# Amp-Rev1.net
KiCad netlist of a schematic drawn in EAGLE
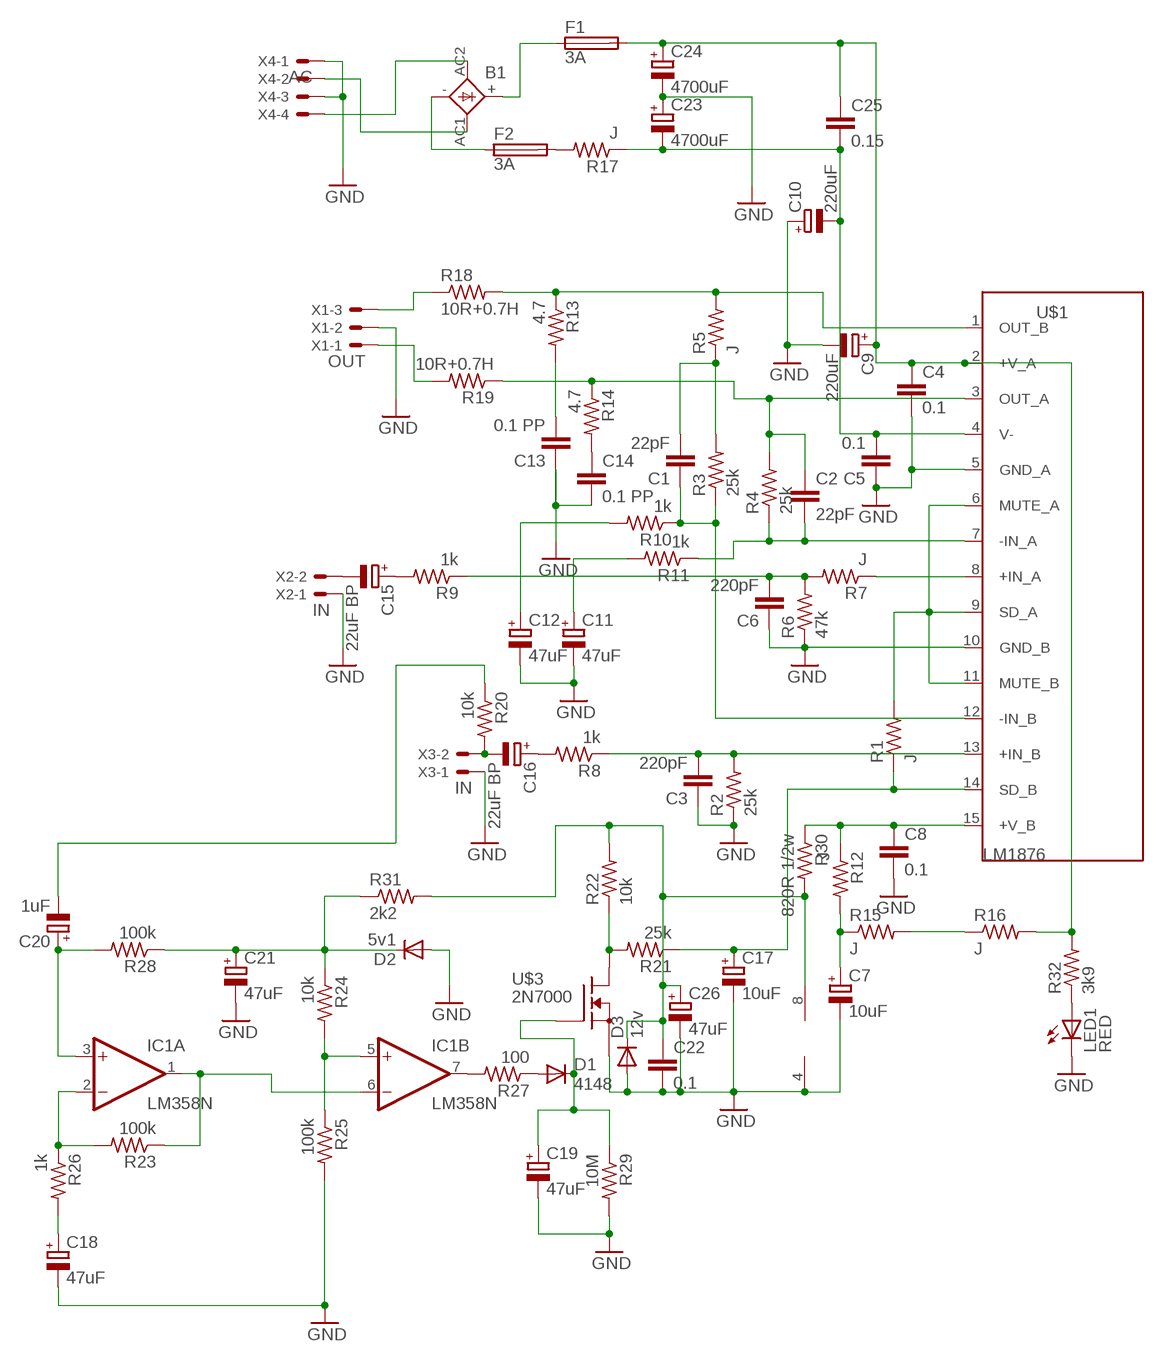
[diagram p0: schematic, sheet 1]

(export (version "E")
  (design (tool "Eeschema 10.0.6"))
  (components
    (comp (ref "B1")
      (value "GBU4")
      (footprint "eagle-import:GBU4S")
      (libsource (lib "eagle-import") (part "GBU4"))
    )
    (comp (ref "C1")
      (value "22pF")
      (footprint "eagle-import:C075-032X103")
      (libsource (lib "eagle-import") (part "C-EU075-032X103"))
    )
    (comp (ref "C2")
      (value "22pF")
      (footprint "eagle-import:C075-032X103")
      (libsource (lib "eagle-import") (part "C-EU075-032X103"))
    )
    (comp (ref "C3")
      (value "220pF")
      (footprint "eagle-import:C1210")
      (libsource (lib "eagle-import") (part "C-EUC1210"))
    )
    (comp (ref "C4")
      (value "0.1")
      (footprint "eagle-import:C050-025X075")
      (libsource (lib "eagle-import") (part "C-EU050-025X075"))
    )
    (comp (ref "C5")
      (value "0.1")
      (footprint "eagle-import:C050-025X075")
      (libsource (lib "eagle-import") (part "C-EU050-025X075"))
    )
    (comp (ref "C6")
      (value "220pF")
      (footprint "eagle-import:C1210")
      (libsource (lib "eagle-import") (part "C-EUC1210"))
    )
    (comp (ref "C7")
      (value "10uF")
      (footprint "eagle-import:E2,5-7")
      (libsource (lib "eagle-import") (part "CPOL-EUE2.5-7"))
    )
    (comp (ref "C8")
      (value "0.1")
      (footprint "eagle-import:C050-025X075")
      (libsource (lib "eagle-import") (part "C-EU050-025X075"))
    )
    (comp (ref "C9")
      (value "220uF")
      (footprint "eagle-import:E5-8,5")
      (libsource (lib "eagle-import") (part "CPOL-EUE5-8.5"))
    )
    (comp (ref "C10")
      (value "220uF")
      (footprint "eagle-import:E5-8,5")
      (libsource (lib "eagle-import") (part "CPOL-EUE5-8.5"))
    )
    (comp (ref "C11")
      (value "47uF")
      (footprint "eagle-import:E2,5-7")
      (libsource (lib "eagle-import") (part "CPOL-EUE2.5-7"))
    )
    (comp (ref "C12")
      (value "47uF")
      (footprint "eagle-import:E2,5-7")
      (libsource (lib "eagle-import") (part "CPOL-EUE2.5-7"))
    )
    (comp (ref "C13")
      (value "0.1 PP")
      (footprint "eagle-import:C050-055X075")
      (libsource (lib "eagle-import") (part "C-EU050-055X075"))
    )
    (comp (ref "C14")
      (value "0.1 PP")
      (footprint "eagle-import:C050-055X075")
      (libsource (lib "eagle-import") (part "C-EU050-055X075"))
    )
    (comp (ref "C15")
      (value "22uF BP")
      (footprint "eagle-import:E2,5-7")
      (libsource (lib "eagle-import") (part "CPOL-EUE2.5-7"))
    )
    (comp (ref "C16")
      (value "22uF BP")
      (footprint "eagle-import:E2,5-7")
      (libsource (lib "eagle-import") (part "CPOL-EUE2.5-7"))
    )
    (comp (ref "C17")
      (value "10uF")
      (footprint "eagle-import:E2,5-6")
      (libsource (lib "eagle-import") (part "CPOL-EUE2.5-6"))
    )
    (comp (ref "C18")
      (value "47uF")
      (footprint "eagle-import:E2,5-7")
      (libsource (lib "eagle-import") (part "CPOL-EUE2.5-7"))
    )
    (comp (ref "C19")
      (value "47uF")
      (footprint "eagle-import:E2,5-7")
      (libsource (lib "eagle-import") (part "CPOL-EUE2.5-7"))
    )
    (comp (ref "C20")
      (value "1uF")
      (footprint "eagle-import:E2,5-6")
      (libsource (lib "eagle-import") (part "CPOL-EUE2.5-6"))
    )
    (comp (ref "C21")
      (value "47uF")
      (footprint "eagle-import:E2,5-7")
      (libsource (lib "eagle-import") (part "CPOL-EUE2.5-7"))
    )
    (comp (ref "C22")
      (value "0.1")
      (footprint "eagle-import:C1206")
      (libsource (lib "eagle-import") (part "C-EUC1206"))
    )
    (comp (ref "C23")
      (value "4700uF")
      (footprint "eagle-import:E7,5-16")
      (libsource (lib "eagle-import") (part "CPOL-EUE7.5-16"))
    )
    (comp (ref "C24")
      (value "4700uF")
      (footprint "eagle-import:E7,5-16")
      (libsource (lib "eagle-import") (part "CPOL-EUE7.5-16"))
    )
    (comp (ref "C25")
      (value "0.15")
      (footprint "eagle-import:C075-032X103")
      (libsource (lib "eagle-import") (part "C-EU075-032X103"))
    )
    (comp (ref "C26")
      (value "47uF")
      (footprint "eagle-import:E2,5-7")
      (libsource (lib "eagle-import") (part "CPOL-EUE2.5-7"))
    )
    (comp (ref "D1")
      (value "4148")
      (footprint "eagle-import:DO35-7")
      (libsource (lib "eagle-import") (part "1N4148DO35-7"))
    )
    (comp (ref "D2")
      (value "5v1")
      (footprint "eagle-import:DO35-10")
      (libsource (lib "eagle-import") (part "1N4148DO35-10"))
    )
    (comp (ref "D3")
      (value "12v")
      (footprint "eagle-import:DO35-10")
      (libsource (lib "eagle-import") (part "1N4148DO35-10"))
    )
    (comp (ref "F1")
      (value "3A")
      (footprint "eagle-import:19560")
      (fields (field (name "MPN") "56000001009"))
      (libsource (lib "eagle-import") (part "19560"))
    )
    (comp (ref "F2")
      (value "3A")
      (footprint "eagle-import:19560")
      (fields (field (name "MPN") "56000001009"))
      (libsource (lib "eagle-import") (part "19560"))
    )
    (comp (ref "IC1")
      (value "LM358N")
      (footprint "eagle-import:DIL08")
      (libsource (lib "eagle-import") (part "LM358N"))
    )
    (comp (ref "LED1")
      (value "RED")
      (footprint "eagle-import:LED3MM")
      (fields (field (name "MF") "VISHAY SEMICONDUCTOR"))
      (libsource (lib "eagle-import") (part "TLLR4400"))
    )
    (comp (ref "R1")
      (value "J")
      (footprint "eagle-import:0207_12")
      (libsource (lib "eagle-import") (part "R-US_0207/12"))
    )
    (comp (ref "R2")
      (value "25k")
      (footprint "eagle-import:R1210")
      (libsource (lib "eagle-import") (part "R-US_R1210"))
    )
    (comp (ref "R3")
      (value "25k")
      (footprint "eagle-import:0207_10")
      (libsource (lib "eagle-import") (part "R-US_0207/10"))
    )
    (comp (ref "R4")
      (value "25k")
      (footprint "eagle-import:0207_10")
      (libsource (lib "eagle-import") (part "R-US_0207/10"))
    )
    (comp (ref "R5")
      (value "J")
      (footprint "eagle-import:0207_10")
      (libsource (lib "eagle-import") (part "R-US_0207/10"))
    )
    (comp (ref "R6")
      (value "47k")
      (footprint "eagle-import:M1206")
      (libsource (lib "eagle-import") (part "R-US_M1206"))
    )
    (comp (ref "R7")
      (value "J")
      (footprint "eagle-import:0204_7")
      (libsource (lib "eagle-import") (part "R-US_0204/7"))
    )
    (comp (ref "R8")
      (value "1k")
      (footprint "eagle-import:0207_10")
      (libsource (lib "eagle-import") (part "R-US_0207/10"))
    )
    (comp (ref "R9")
      (value "1k")
      (footprint "eagle-import:0207_12")
      (libsource (lib "eagle-import") (part "R-US_0207/12"))
    )
    (comp (ref "R10")
      (value "1k")
      (footprint "eagle-import:0204_7")
      (libsource (lib "eagle-import") (part "R-US_0204/7"))
    )
    (comp (ref "R11")
      (value "1k")
      (footprint "eagle-import:0207_10")
      (libsource (lib "eagle-import") (part "R-US_0207/10"))
    )
    (comp (ref "R12")
      (value "J")
      (footprint "eagle-import:0207_12")
      (libsource (lib "eagle-import") (part "R-US_0207/12"))
    )
    (comp (ref "R13")
      (value "4.7")
      (footprint "eagle-import:0207_12")
      (libsource (lib "eagle-import") (part "R-US_0207/12"))
    )
    (comp (ref "R14")
      (value "4.7")
      (footprint "eagle-import:0207_12")
      (libsource (lib "eagle-import") (part "R-US_0207/12"))
    )
    (comp (ref "R15")
      (value "J")
      (footprint "eagle-import:0207_12")
      (libsource (lib "eagle-import") (part "R-US_0207/12"))
    )
    (comp (ref "R16")
      (value "J")
      (footprint "eagle-import:0207_12")
      (libsource (lib "eagle-import") (part "R-US_0207/12"))
    )
    (comp (ref "R17")
      (value "J")
      (footprint "eagle-import:0207_10")
      (libsource (lib "eagle-import") (part "R-US_0207/10"))
    )
    (comp (ref "R18")
      (value "10R+0.7H")
      (footprint "eagle-import:0207_12")
      (libsource (lib "eagle-import") (part "R-US_0207/12"))
    )
    (comp (ref "R19")
      (value "10R+0.7H")
      (footprint "eagle-import:0207_12")
      (libsource (lib "eagle-import") (part "R-US_0207/12"))
    )
    (comp (ref "R20")
      (value "10k")
      (footprint "eagle-import:0204_7")
      (libsource (lib "eagle-import") (part "R-US_0204/7"))
    )
    (comp (ref "R21")
      (value "25k")
      (footprint "eagle-import:0204_7")
      (libsource (lib "eagle-import") (part "R-US_0204/7"))
    )
    (comp (ref "R22")
      (value "10k")
      (footprint "eagle-import:0204_7")
      (libsource (lib "eagle-import") (part "R-US_0204/7"))
    )
    (comp (ref "R23")
      (value "100k")
      (footprint "eagle-import:0204_5")
      (libsource (lib "eagle-import") (part "R-US_0204/5"))
    )
    (comp (ref "R24")
      (value "10k")
      (footprint "eagle-import:0207_10")
      (libsource (lib "eagle-import") (part "R-US_0207/10"))
    )
    (comp (ref "R25")
      (value "100k")
      (footprint "eagle-import:0204_5")
      (libsource (lib "eagle-import") (part "R-US_0204/5"))
    )
    (comp (ref "R26")
      (value "1k")
      (footprint "eagle-import:0207_10")
      (libsource (lib "eagle-import") (part "R-US_0207/10"))
    )
    (comp (ref "R27")
      (value "100")
      (footprint "eagle-import:0204_7")
      (libsource (lib "eagle-import") (part "R-US_0204/7"))
    )
    (comp (ref "R28")
      (value "100k")
      (footprint "eagle-import:0204_5")
      (libsource (lib "eagle-import") (part "R-US_0204/5"))
    )
    (comp (ref "R29")
      (value "10M")
      (footprint "eagle-import:0207_10")
      (libsource (lib "eagle-import") (part "R-US_0207/10"))
    )
    (comp (ref "R30")
      (value "820R 1/2w")
      (footprint "eagle-import:0207_10")
      (libsource (lib "eagle-import") (part "R-US_0207/10"))
    )
    (comp (ref "R31")
      (value "2k2")
      (footprint "eagle-import:0309_10")
      (libsource (lib "eagle-import") (part "R-US_0309/10"))
    )
    (comp (ref "R32")
      (value "3k9")
      (footprint "eagle-import:0207_10")
      (libsource (lib "eagle-import") (part "R-US_0207/10"))
    )
    (comp (ref "U$1")
      (value "LM1876")
      (footprint "eagle-import:MULTIWATT-15")
      (libsource (lib "eagle-import") (part "LM1876"))
    )
    (comp (ref "U$3")
      (value "2N7000")
      (footprint "eagle-import:TO92-")
      (libsource (lib "eagle-import") (part "2N7000"))
    )
    (comp (ref "X1")
      (value "OUT")
      (footprint "eagle-import:22-23-2031")
      (fields (field (name "MF") "MOLEX") (field (name "MPN") "22-23-2031"))
      (libsource (lib "eagle-import") (part "22-23-2031"))
    )
    (comp (ref "X2")
      (value "IN")
      (footprint "eagle-import:22-23-2021")
      (fields (field (name "MF") "MOLEX") (field (name "MPN") "22-23-2021"))
      (libsource (lib "eagle-import") (part "22-23-2021"))
    )
    (comp (ref "X3")
      (value "IN")
      (footprint "eagle-import:22-23-2021")
      (fields (field (name "MF") "MOLEX") (field (name "MPN") "22-23-2021"))
      (libsource (lib "eagle-import") (part "22-23-2021"))
    )
    (comp (ref "X4")
      (value "AC")
      (footprint "eagle-import:5566-4")
      (libsource (lib "eagle-import") (part "5566-4"))
    )
  )
  (nets
    (net (code "1") (name "GND") (class "Default")
      (node (ref "C10") (pin "+") (pinfunction "+_+") (pintype "passive"))
      (node (ref "C11") (pin "-") (pinfunction "-_-") (pintype "passive"))
      (node (ref "C12") (pin "-") (pinfunction "-_-") (pintype "passive"))
      (node (ref "C13") (pin "1") (pinfunction "1_1") (pintype "passive"))
      (node (ref "C14") (pin "2") (pinfunction "2_2") (pintype "passive"))
      (node (ref "C17") (pin "-") (pinfunction "-_-") (pintype "passive"))
      (node (ref "C18") (pin "-") (pinfunction "-_-") (pintype "passive"))
      (node (ref "C19") (pin "-") (pinfunction "-_-") (pintype "passive"))
      (node (ref "C21") (pin "-") (pinfunction "-_-") (pintype "passive"))
      (node (ref "C22") (pin "2") (pinfunction "2_2") (pintype "passive"))
      (node (ref "C23") (pin "+") (pinfunction "+_+") (pintype "passive"))
      (node (ref "C24") (pin "-") (pinfunction "-_-") (pintype "passive"))
      (node (ref "C26") (pin "-") (pinfunction "-_-") (pintype "passive"))
      (node (ref "C3") (pin "1") (pinfunction "1_1") (pintype "passive"))
      (node (ref "C4") (pin "2") (pinfunction "2_2") (pintype "passive"))
      (node (ref "C5") (pin "1") (pinfunction "1_1") (pintype "passive"))
      (node (ref "C6") (pin "1") (pinfunction "1_1") (pintype "passive"))
      (node (ref "C7") (pin "-") (pinfunction "-_-") (pintype "passive"))
      (node (ref "C8") (pin "2") (pinfunction "2_2") (pintype "passive"))
      (node (ref "C9") (pin "-") (pinfunction "-_-") (pintype "passive"))
      (node (ref "D2") (pin "A") (pinfunction "A_A") (pintype "passive"))
      (node (ref "D3") (pin "A") (pinfunction "A_A") (pintype "passive"))
      (node (ref "IC1") (pin "4") (pinfunction "V-_4") (pintype "power_in"))
      (node (ref "LED1") (pin "K") (pinfunction "C_K") (pintype "passive"))
      (node (ref "R2") (pin "1") (pinfunction "1_1") (pintype "passive"))
      (node (ref "R25") (pin "2") (pinfunction "2_2") (pintype "passive"))
      (node (ref "R29") (pin "2") (pinfunction "2_2") (pintype "passive"))
      (node (ref "R6") (pin "1") (pinfunction "1_1") (pintype "passive"))
      (node (ref "U$1") (pin "10") (pinfunction "GND_B_10") (pintype "passive"))
      (node (ref "U$1") (pin "5") (pinfunction "GND_A_5") (pintype "passive"))
      (node (ref "U$3") (pin "3") (pinfunction "S_3") (pintype "passive"))
      (node (ref "X1") (pin "2") (pinfunction "S_2") (pintype "passive"))
      (node (ref "X2") (pin "1") (pinfunction "S_1") (pintype "passive"))
      (node (ref "X3") (pin "1") (pinfunction "S_1") (pintype "passive"))
      (node (ref "X4") (pin "1") (pinfunction "S_1") (pintype "passive"))
      (node (ref "X4") (pin "3") (pinfunction "S_3") (pintype "passive"))
    )
    (net (code "2") (name "Net-(B1-AC1)") (class "Default")
      (node (ref "B1") (pin "AC2") (pinfunction "AC1_AC2") (pintype "passive"))
      (node (ref "X4") (pin "4") (pinfunction "S_4") (pintype "passive"))
    )
    (net (code "3") (name "Net-(B1-AC2)") (class "Default")
      (node (ref "B1") (pin "AC1") (pinfunction "AC2_AC1") (pintype "passive"))
      (node (ref "X4") (pin "2") (pinfunction "S_2") (pintype "passive"))
    )
    (net (code "4") (name "Net-(B1-Pad+)") (class "Default")
      (node (ref "B1") (pin "+") (pinfunction "+_+") (pintype "passive"))
      (node (ref "F1") (pin "1") (pinfunction "1_1") (pintype "passive"))
    )
    (net (code "5") (name "Net-(B1-Pad-)") (class "Default")
      (node (ref "B1") (pin "-") (pinfunction "-_-") (pintype "passive"))
      (node (ref "F2") (pin "1") (pinfunction "1_1") (pintype "passive"))
    )
    (net (code "6") (name "Net-(C1-Pad2)") (class "Default")
      (node (ref "C1") (pin "2") (pinfunction "2_2") (pintype "passive"))
      (node (ref "R3") (pin "2") (pinfunction "2_2") (pintype "passive"))
      (node (ref "R5") (pin "1") (pinfunction "1_1") (pintype "passive"))
    )
    (net (code "7") (name "Net-(C6-Pad2)") (class "Default")
      (node (ref "C6") (pin "2") (pinfunction "2_2") (pintype "passive"))
      (node (ref "R6") (pin "2") (pinfunction "2_2") (pintype "passive"))
      (node (ref "R7") (pin "2") (pinfunction "2_2") (pintype "passive"))
      (node (ref "R9") (pin "1") (pinfunction "1_1") (pintype "passive"))
    )
    (net (code "8") (name "Net-(C7-Pad+)") (class "Default")
      (node (ref "C7") (pin "+") (pinfunction "+_+") (pintype "passive"))
      (node (ref "R12") (pin "2") (pinfunction "2_2") (pintype "passive"))
      (node (ref "R15") (pin "1") (pinfunction "1_1") (pintype "passive"))
    )
    (net (code "9") (name "Net-(C11-Pad+)") (class "Default")
      (node (ref "C11") (pin "+") (pinfunction "+_+") (pintype "passive"))
      (node (ref "R11") (pin "2") (pinfunction "2_2") (pintype "passive"))
    )
    (net (code "10") (name "Net-(C12-Pad+)") (class "Default")
      (node (ref "C12") (pin "+") (pinfunction "+_+") (pintype "passive"))
      (node (ref "R10") (pin "2") (pinfunction "2_2") (pintype "passive"))
    )
    (net (code "11") (name "Net-(C13-Pad2)") (class "Default")
      (node (ref "C13") (pin "2") (pinfunction "2_2") (pintype "passive"))
      (node (ref "R13") (pin "2") (pinfunction "2_2") (pintype "passive"))
    )
    (net (code "12") (name "Net-(C14-Pad1)") (class "Default")
      (node (ref "C14") (pin "1") (pinfunction "1_1") (pintype "passive"))
      (node (ref "R14") (pin "2") (pinfunction "2_2") (pintype "passive"))
    )
    (net (code "13") (name "Net-(C15-Pad+)") (class "Default")
      (node (ref "C15") (pin "+") (pinfunction "+_+") (pintype "passive"))
      (node (ref "R9") (pin "2") (pinfunction "2_2") (pintype "passive"))
    )
    (net (code "14") (name "Net-(C16-Pad+)") (class "Default")
      (node (ref "C16") (pin "+") (pinfunction "+_+") (pintype "passive"))
      (node (ref "R8") (pin "2") (pinfunction "2_2") (pintype "passive"))
    )
    (net (code "15") (name "Net-(C18-Pad+)") (class "Default")
      (node (ref "C18") (pin "+") (pinfunction "+_+") (pintype "passive"))
      (node (ref "R26") (pin "2") (pinfunction "2_2") (pintype "passive"))
    )
    (net (code "16") (name "Net-(C20-Pad-)") (class "Default")
      (node (ref "C20") (pin "-") (pinfunction "-_-") (pintype "passive"))
      (node (ref "R20") (pin "1") (pinfunction "1_1") (pintype "passive"))
    )
    (net (code "17") (name "Net-(C21-Pad+)") (class "Default")
      (node (ref "C21") (pin "+") (pinfunction "+_+") (pintype "passive"))
      (node (ref "D2") (pin "C") (pinfunction "C_C") (pintype "passive"))
      (node (ref "R24") (pin "1") (pinfunction "1_1") (pintype "passive"))
      (node (ref "R28") (pin "1") (pinfunction "1_1") (pintype "passive"))
      (node (ref "R31") (pin "1") (pinfunction "1_1") (pintype "passive"))
    )
    (net (code "18") (name "Net-(D1-PadA)") (class "Default")
      (node (ref "D1") (pin "A") (pinfunction "A_A") (pintype "passive"))
      (node (ref "R27") (pin "1") (pinfunction "1_1") (pintype "passive"))
    )
    (net (code "19") (name "Net-(F2-Pad2)") (class "Default")
      (node (ref "F2") (pin "2") (pinfunction "2_2") (pintype "passive"))
      (node (ref "R17") (pin "2") (pinfunction "2_2") (pintype "passive"))
    )
    (net (code "20") (name "Net-(IC1A-+IN)") (class "Default")
      (node (ref "C20") (pin "+") (pinfunction "+_+") (pintype "passive"))
      (node (ref "IC1") (pin "3") (pinfunction "+IN_3") (pintype "input"))
      (node (ref "R28") (pin "2") (pinfunction "2_2") (pintype "passive"))
    )
    (net (code "21") (name "Net-(IC1A--IN)") (class "Default")
      (node (ref "IC1") (pin "2") (pinfunction "-IN_2") (pintype "input"))
      (node (ref "R23") (pin "2") (pinfunction "2_2") (pintype "passive"))
      (node (ref "R26") (pin "1") (pinfunction "1_1") (pintype "passive"))
    )
    (net (code "22") (name "Net-(IC1A-OUT)") (class "Default")
      (node (ref "IC1") (pin "1") (pinfunction "OUT_1") (pintype "output"))
      (node (ref "IC1") (pin "6") (pinfunction "-IN_6") (pintype "input"))
      (node (ref "R23") (pin "1") (pinfunction "1_1") (pintype "passive"))
    )
    (net (code "23") (name "Net-(IC1B-+IN)") (class "Default")
      (node (ref "IC1") (pin "5") (pinfunction "+IN_5") (pintype "input"))
      (node (ref "R24") (pin "2") (pinfunction "2_2") (pintype "passive"))
      (node (ref "R25") (pin "1") (pinfunction "1_1") (pintype "passive"))
    )
    (net (code "24") (name "Net-(IC1B-OUT)") (class "Default")
      (node (ref "IC1") (pin "7") (pinfunction "OUT_7") (pintype "output"))
      (node (ref "R27") (pin "2") (pinfunction "2_2") (pintype "passive"))
    )
    (net (code "25") (name "Net-(IC1C-V+)") (class "Default")
      (node (ref "C22") (pin "1") (pinfunction "1_1") (pintype "passive"))
      (node (ref "C26") (pin "+") (pinfunction "+_+") (pintype "passive"))
      (node (ref "D3") (pin "C") (pinfunction "C_C") (pintype "passive"))
      (node (ref "IC1") (pin "8") (pinfunction "V+_8") (pintype "power_in"))
      (node (ref "R22") (pin "2") (pinfunction "2_2") (pintype "passive"))
      (node (ref "R30") (pin "2") (pinfunction "2_2") (pintype "passive"))
      (node (ref "R31") (pin "2") (pinfunction "2_2") (pintype "passive"))
    )
    (net (code "26") (name "Net-(LED1-PadA)") (class "Default")
      (node (ref "LED1") (pin "A") (pinfunction "A_A") (pintype "passive"))
      (node (ref "R32") (pin "1") (pinfunction "1_1") (pintype "passive"))
    )
    (net (code "27") (name "Net-(R15-Pad2)") (class "Default")
      (node (ref "R15") (pin "2") (pinfunction "2_2") (pintype "passive"))
      (node (ref "R16") (pin "1") (pinfunction "1_1") (pintype "passive"))
    )
    (net (code "28") (name "Net-(U$1-+IN_A)") (class "Default")
      (node (ref "R7") (pin "1") (pinfunction "1_1") (pintype "passive"))
      (node (ref "U$1") (pin "8") (pinfunction "+IN_A_8") (pintype "passive"))
    )
    (net (code "29") (name "Net-(U$1-+IN_B)") (class "Default")
      (node (ref "C3") (pin "2") (pinfunction "2_2") (pintype "passive"))
      (node (ref "R2") (pin "2") (pinfunction "2_2") (pintype "passive"))
      (node (ref "R8") (pin "1") (pinfunction "1_1") (pintype "passive"))
      (node (ref "U$1") (pin "13") (pinfunction "+IN_B_13") (pintype "passive"))
    )
    (net (code "30") (name "Net-(U$1-+V_A)") (class "Default")
      (node (ref "C24") (pin "+") (pinfunction "+_+") (pintype "passive"))
      (node (ref "C25") (pin "1") (pinfunction "1_1") (pintype "passive"))
      (node (ref "C4") (pin "1") (pinfunction "1_1") (pintype "passive"))
      (node (ref "C9") (pin "+") (pinfunction "+_+") (pintype "passive"))
      (node (ref "F1") (pin "2") (pinfunction "2_2") (pintype "passive"))
      (node (ref "R16") (pin "2") (pinfunction "2_2") (pintype "passive"))
      (node (ref "R32") (pin "2") (pinfunction "2_2") (pintype "passive"))
      (node (ref "U$1") (pin "2") (pinfunction "+V_A_2") (pintype "passive"))
    )
    (net (code "31") (name "Net-(U$1-+V_B)") (class "Default")
      (node (ref "C8") (pin "1") (pinfunction "1_1") (pintype "passive"))
      (node (ref "R12") (pin "1") (pinfunction "1_1") (pintype "passive"))
      (node (ref "R30") (pin "1") (pinfunction "1_1") (pintype "passive"))
      (node (ref "U$1") (pin "15") (pinfunction "+V_B_15") (pintype "passive"))
    )
    (net (code "32") (name "Net-(U$1--IN_A)") (class "Default")
      (node (ref "C2") (pin "2") (pinfunction "2_2") (pintype "passive"))
      (node (ref "R11") (pin "1") (pinfunction "1_1") (pintype "passive"))
      (node (ref "R4") (pin "1") (pinfunction "1_1") (pintype "passive"))
      (node (ref "U$1") (pin "7") (pinfunction "-IN_A_7") (pintype "passive"))
    )
    (net (code "33") (name "Net-(U$1--IN_B)") (class "Default")
      (node (ref "C1") (pin "1") (pinfunction "1_1") (pintype "passive"))
      (node (ref "R10") (pin "1") (pinfunction "1_1") (pintype "passive"))
      (node (ref "R3") (pin "1") (pinfunction "1_1") (pintype "passive"))
      (node (ref "U$1") (pin "12") (pinfunction "-IN_B_12") (pintype "passive"))
    )
    (net (code "34") (name "Net-(U$1-MUTE_A)") (class "Default")
      (node (ref "R1") (pin "2") (pinfunction "2_2") (pintype "passive"))
      (node (ref "U$1") (pin "11") (pinfunction "MUTE_B_11") (pintype "passive"))
      (node (ref "U$1") (pin "6") (pinfunction "MUTE_A_6") (pintype "passive"))
      (node (ref "U$1") (pin "9") (pinfunction "SD_A_9") (pintype "passive"))
    )
    (net (code "35") (name "Net-(U$1-OUT_A)") (class "Default")
      (node (ref "C2") (pin "1") (pinfunction "1_1") (pintype "passive"))
      (node (ref "R14") (pin "1") (pinfunction "1_1") (pintype "passive"))
      (node (ref "R19") (pin "1") (pinfunction "1_1") (pintype "passive"))
      (node (ref "R4") (pin "2") (pinfunction "2_2") (pintype "passive"))
      (node (ref "U$1") (pin "3") (pinfunction "OUT_A_3") (pintype "passive"))
    )
    (net (code "36") (name "Net-(U$1-OUT_B)") (class "Default")
      (node (ref "R13") (pin "1") (pinfunction "1_1") (pintype "passive"))
      (node (ref "R18") (pin "2") (pinfunction "2_2") (pintype "passive"))
      (node (ref "R5") (pin "2") (pinfunction "2_2") (pintype "passive"))
      (node (ref "U$1") (pin "1") (pinfunction "OUT_B_1") (pintype "passive"))
    )
    (net (code "37") (name "Net-(U$1-SD_B)") (class "Default")
      (node (ref "C17") (pin "+") (pinfunction "+_+") (pintype "passive"))
      (node (ref "R1") (pin "1") (pinfunction "1_1") (pintype "passive"))
      (node (ref "R21") (pin "1") (pinfunction "1_1") (pintype "passive"))
      (node (ref "U$1") (pin "14") (pinfunction "SD_B_14") (pintype "passive"))
    )
    (net (code "38") (name "Net-(U$1-V-)") (class "Default")
      (node (ref "C10") (pin "-") (pinfunction "-_-") (pintype "passive"))
      (node (ref "C23") (pin "-") (pinfunction "-_-") (pintype "passive"))
      (node (ref "C25") (pin "2") (pinfunction "2_2") (pintype "passive"))
      (node (ref "C5") (pin "2") (pinfunction "2_2") (pintype "passive"))
      (node (ref "R17") (pin "1") (pinfunction "1_1") (pintype "passive"))
      (node (ref "U$1") (pin "4") (pinfunction "V-_4") (pintype "passive"))
    )
    (net (code "39") (name "Net-(U$3-D)") (class "Default")
      (node (ref "R21") (pin "2") (pinfunction "2_2") (pintype "passive"))
      (node (ref "R22") (pin "1") (pinfunction "1_1") (pintype "passive"))
      (node (ref "U$3") (pin "1") (pinfunction "D_1") (pintype "passive"))
    )
    (net (code "40") (name "Net-(U$3-G)") (class "Default")
      (node (ref "C19") (pin "+") (pinfunction "+_+") (pintype "passive"))
      (node (ref "D1") (pin "C") (pinfunction "C_C") (pintype "passive"))
      (node (ref "R29") (pin "1") (pinfunction "1_1") (pintype "passive"))
      (node (ref "U$3") (pin "2") (pinfunction "G_2") (pintype "passive"))
    )
    (net (code "41") (name "Net-(X1A-S)") (class "Default")
      (node (ref "R19") (pin "2") (pinfunction "2_2") (pintype "passive"))
      (node (ref "X1") (pin "1") (pinfunction "S_1") (pintype "passive"))
    )
    (net (code "42") (name "Net-(X1C-S)") (class "Default")
      (node (ref "R18") (pin "1") (pinfunction "1_1") (pintype "passive"))
      (node (ref "X1") (pin "3") (pinfunction "S_3") (pintype "passive"))
    )
    (net (code "43") (name "Net-(X2B-S)") (class "Default")
      (node (ref "C15") (pin "-") (pinfunction "-_-") (pintype "passive"))
      (node (ref "X2") (pin "2") (pinfunction "S_2") (pintype "passive"))
    )
    (net (code "44") (name "Net-(X3B-S)") (class "Default")
      (node (ref "C16") (pin "-") (pinfunction "-_-") (pintype "passive"))
      (node (ref "R20") (pin "2") (pinfunction "2_2") (pintype "passive"))
      (node (ref "X3") (pin "2") (pinfunction "S_2") (pintype "passive"))
    )
  )
)
